# ElectronicCompass_T05.net
KiCad netlist of a schematic drawn in EAGLE
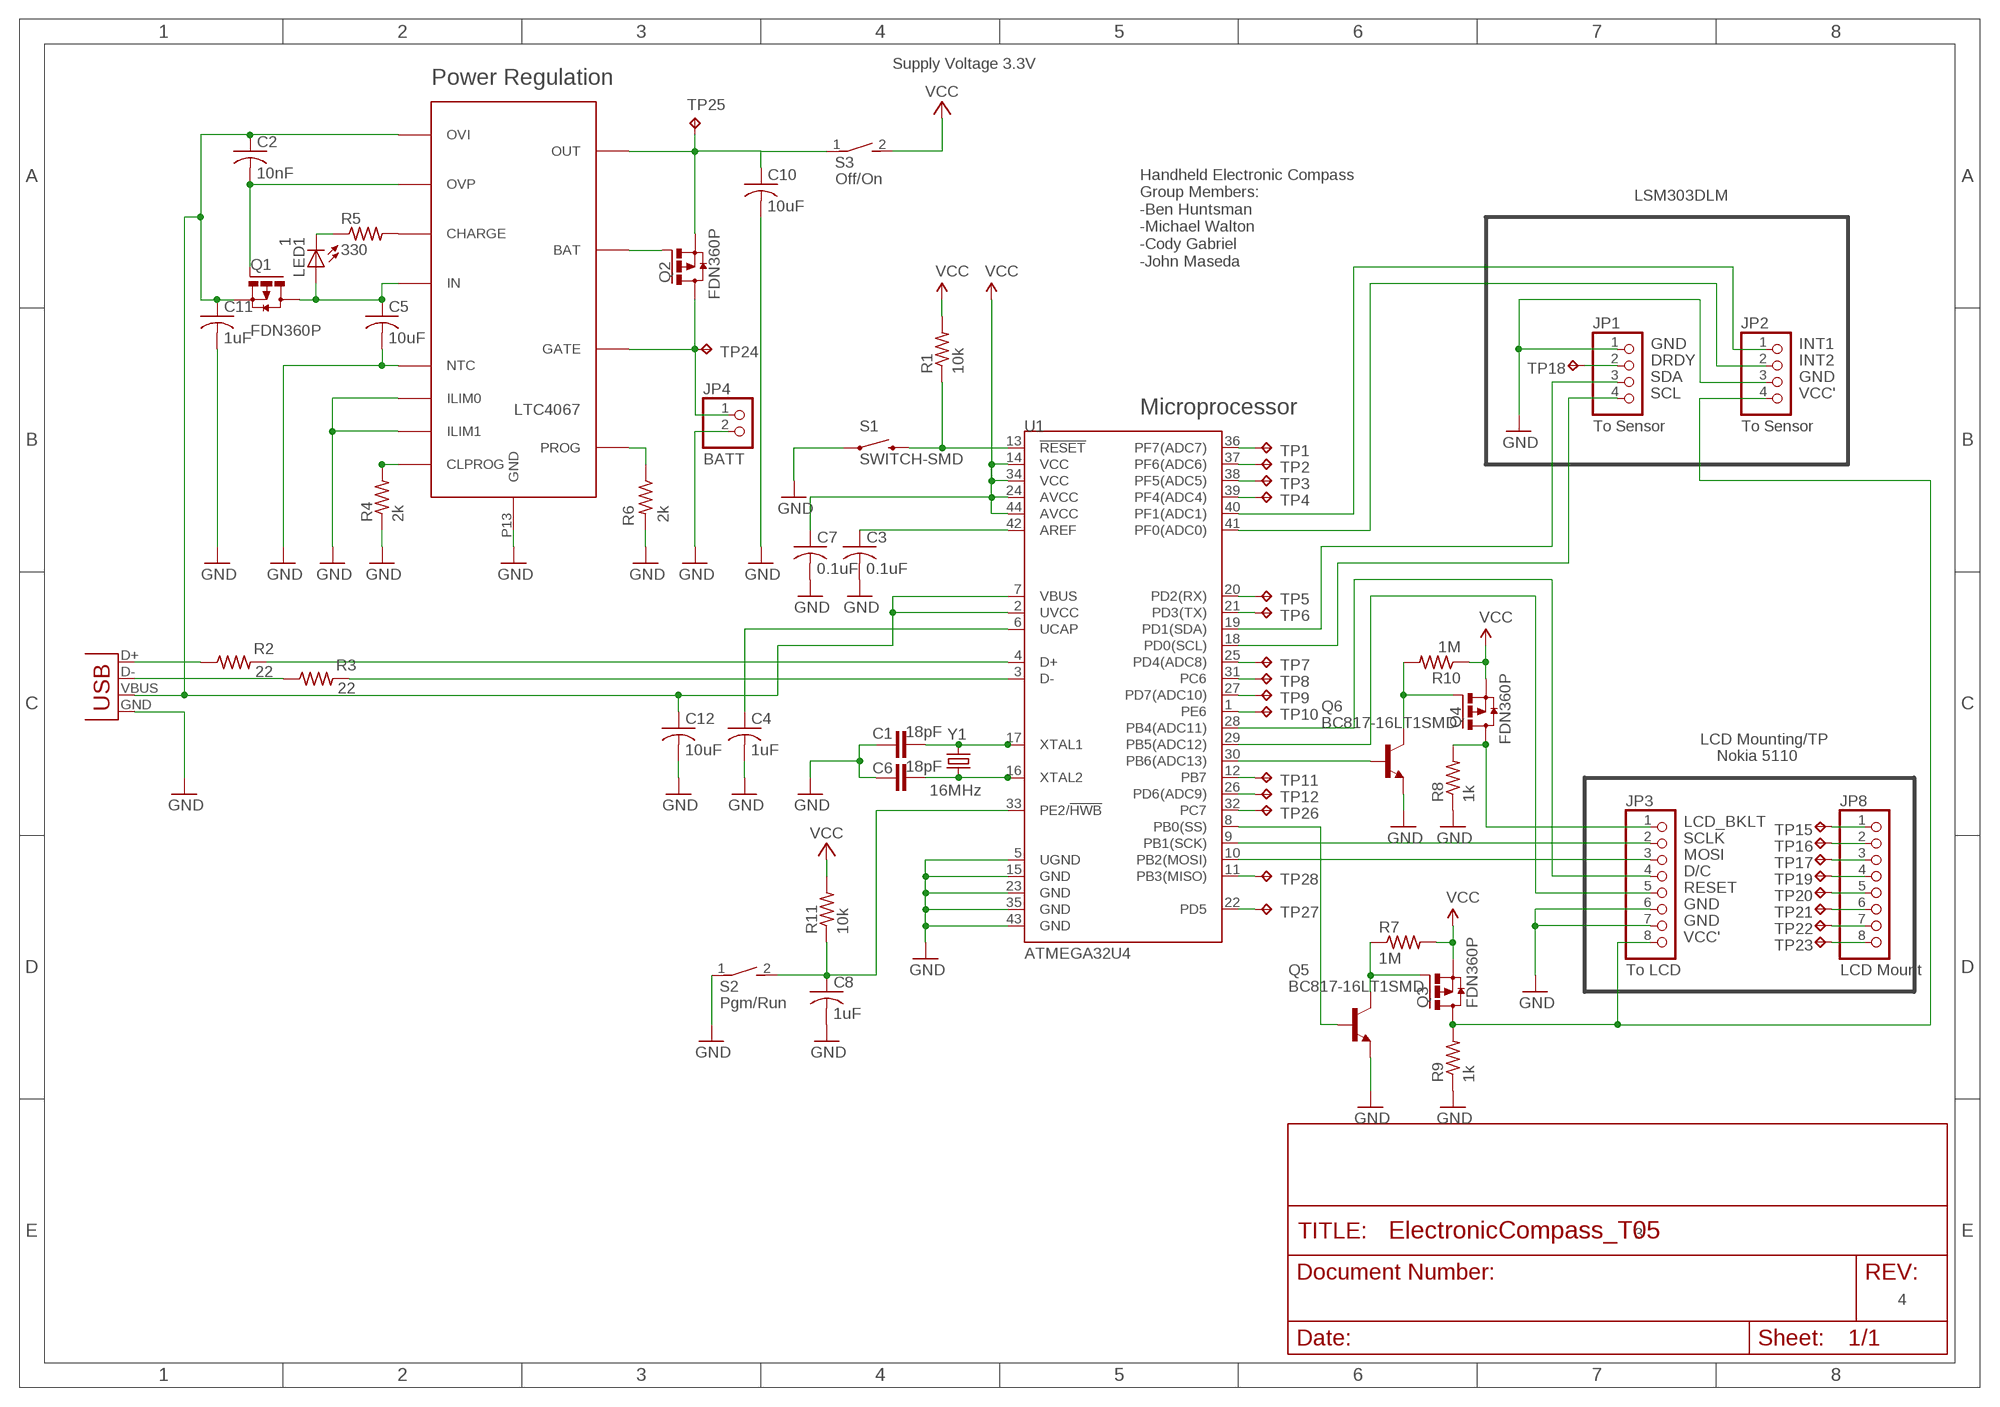
[diagram p0: schematic, sheet 1]

(export (version "E")
  (design (tool "Eeschema 10.0.6"))
  (components
    (comp (ref "C1")
      (value "18pF")
      (footprint "eagle-import:0402-CAP")
      (libsource (lib "eagle-import") (part "CAP0402-CAP"))
    )
    (comp (ref "C2")
      (value "10nF")
      (footprint "eagle-import:C0805")
      (libsource (lib "eagle-import") (part "C-USC0805"))
    )
    (comp (ref "C3")
      (value "0.1uF")
      (footprint "eagle-import:C0805")
      (libsource (lib "eagle-import") (part "C-USC0805"))
    )
    (comp (ref "C4")
      (value "1uF")
      (footprint "eagle-import:C0805")
      (libsource (lib "eagle-import") (part "C-USC0805"))
    )
    (comp (ref "C5")
      (value "10uF")
      (footprint "eagle-import:C0805")
      (libsource (lib "eagle-import") (part "C-USC0805"))
    )
    (comp (ref "C6")
      (value "18pF")
      (footprint "eagle-import:0402-CAP")
      (libsource (lib "eagle-import") (part "CAP0402-CAP"))
    )
    (comp (ref "C7")
      (value "0.1uF")
      (footprint "eagle-import:C0805")
      (libsource (lib "eagle-import") (part "C-USC0805"))
    )
    (comp (ref "C8")
      (value "1uF")
      (footprint "eagle-import:C0805")
      (libsource (lib "eagle-import") (part "C-USC0805"))
    )
    (comp (ref "C10")
      (value "10uF")
      (footprint "eagle-import:C0805")
      (libsource (lib "eagle-import") (part "C-USC0805"))
    )
    (comp (ref "C11")
      (value "1uF")
      (footprint "eagle-import:C0805")
      (libsource (lib "eagle-import") (part "C-USC0805"))
    )
    (comp (ref "C12")
      (value "10uF")
      (footprint "eagle-import:C0805")
      (libsource (lib "eagle-import") (part "C-USC0805"))
    )
    (comp (ref "JP1")
      (value "To Sensor")
      (footprint "eagle-import:1X04")
      (libsource (lib "eagle-import") (part "PINHD-1X4"))
    )
    (comp (ref "JP2")
      (value "To Sensor")
      (footprint "eagle-import:1X04")
      (libsource (lib "eagle-import") (part "PINHD-1X4"))
    )
    (comp (ref "JP3")
      (value "To LCD")
      (footprint "eagle-import:1X08")
      (libsource (lib "eagle-import") (part "PINHD-1X8"))
    )
    (comp (ref "JP4")
      (value "BATT")
      (footprint "eagle-import:1X02")
      (libsource (lib "eagle-import") (part "PINHD-1X2"))
    )
    (comp (ref "JP8")
      (value "LCD Mount")
      (footprint "eagle-import:1X08")
      (libsource (lib "eagle-import") (part "PINHD-1X8"))
    )
    (comp (ref "LED1")
      (value "1")
      (footprint "eagle-import:CHIPLED_0805")
      (libsource (lib "eagle-import") (part "LEDCHIPLED_0805"))
    )
    (comp (ref "Q1")
      (value "FDN360P")
      (footprint "eagle-import:SUPER-SOT3")
      (libsource (lib "eagle-import") (part "FDN360P"))
    )
    (comp (ref "Q2")
      (value "FDN360P")
      (footprint "eagle-import:SUPER-SOT3")
      (libsource (lib "eagle-import") (part "FDN360P"))
    )
    (comp (ref "Q3")
      (value "FDN360P")
      (footprint "eagle-import:SUPER-SOT3")
      (libsource (lib "eagle-import") (part "FDN360P"))
    )
    (comp (ref "Q4")
      (value "FDN360P")
      (footprint "eagle-import:SUPER-SOT3")
      (libsource (lib "eagle-import") (part "FDN360P"))
    )
    (comp (ref "Q5")
      (value "BC817-16LT1SMD")
      (footprint "eagle-import:SOT23-BEC")
      (libsource (lib "eagle-import") (part "BC817SMD-16LT1"))
    )
    (comp (ref "Q6")
      (value "BC817-16LT1SMD")
      (footprint "eagle-import:SOT23-BEC")
      (libsource (lib "eagle-import") (part "BC817SMD-16LT1"))
    )
    (comp (ref "R1")
      (value "10k")
      (footprint "eagle-import:M0805")
      (libsource (lib "eagle-import") (part "resistor_R-US_M0805"))
    )
    (comp (ref "R2")
      (value "22")
      (footprint "eagle-import:M0805")
      (libsource (lib "eagle-import") (part "resistor_R-US_M0805"))
    )
    (comp (ref "R3")
      (value "22")
      (footprint "eagle-import:M0805")
      (libsource (lib "eagle-import") (part "resistor_R-US_M0805"))
    )
    (comp (ref "R4")
      (value "2k")
      (footprint "eagle-import:M0805")
      (libsource (lib "eagle-import") (part "resistor_R-US_M0805"))
    )
    (comp (ref "R5")
      (value "330")
      (footprint "eagle-import:M0805")
      (libsource (lib "eagle-import") (part "resistor_R-US_M0805"))
    )
    (comp (ref "R6")
      (value "2k")
      (footprint "eagle-import:M0805")
      (libsource (lib "eagle-import") (part "resistor_R-US_M0805"))
    )
    (comp (ref "R7")
      (value "1M")
      (footprint "eagle-import:M0805")
      (libsource (lib "eagle-import") (part "resistor_R-US_M0805"))
    )
    (comp (ref "R8")
      (value "1k")
      (footprint "eagle-import:M0805")
      (libsource (lib "eagle-import") (part "R-US_M0805"))
    )
    (comp (ref "R9")
      (value "1k")
      (footprint "eagle-import:M0805")
      (libsource (lib "eagle-import") (part "resistor_R-US_M0805"))
    )
    (comp (ref "R10")
      (value "1M")
      (footprint "eagle-import:M0805")
      (libsource (lib "eagle-import") (part "resistor_R-US_M0805"))
    )
    (comp (ref "R11")
      (value "10k")
      (footprint "eagle-import:M0805")
      (libsource (lib "eagle-import") (part "resistor_R-US_M0805"))
    )
    (comp (ref "S1")
      (value "SWITCH-SMD")
      (footprint "eagle-import:TACTILE_SWITCH_SMD")
      (libsource (lib "eagle-import") (part "SWITCH-MOMENTARY-2SMD"))
    )
    (comp (ref "S2")
      (value "Pgm/Run")
      (footprint "eagle-import:DS-01")
      (libsource (lib "eagle-import") (part "DS01E"))
    )
    (comp (ref "S3")
      (value "Off/On")
      (footprint "eagle-import:DS-01")
      (libsource (lib "eagle-import") (part "DS01E"))
    )
    (comp (ref "TP1")
      (value "TPTP06R")
      (footprint "eagle-import:TP06R")
      (libsource (lib "eagle-import") (part "TPTP06R"))
    )
    (comp (ref "TP2")
      (value "TPTP06R")
      (footprint "eagle-import:TP06R")
      (libsource (lib "eagle-import") (part "TPTP06R"))
    )
    (comp (ref "TP3")
      (value "TPTP06R")
      (footprint "eagle-import:TP06R")
      (libsource (lib "eagle-import") (part "TPTP06R"))
    )
    (comp (ref "TP4")
      (value "TPTP06R")
      (footprint "eagle-import:TP06R")
      (libsource (lib "eagle-import") (part "TPTP06R"))
    )
    (comp (ref "TP5")
      (value "TPTP06R")
      (footprint "eagle-import:TP06R")
      (libsource (lib "eagle-import") (part "TPTP06R"))
    )
    (comp (ref "TP6")
      (value "TPTP06R")
      (footprint "eagle-import:TP06R")
      (libsource (lib "eagle-import") (part "TPTP06R"))
    )
    (comp (ref "TP7")
      (value "TPTP06R")
      (footprint "eagle-import:TP06R")
      (libsource (lib "eagle-import") (part "TPTP06R"))
    )
    (comp (ref "TP8")
      (value "TPTP06R")
      (footprint "eagle-import:TP06R")
      (libsource (lib "eagle-import") (part "TPTP06R"))
    )
    (comp (ref "TP9")
      (value "TPTP06R")
      (footprint "eagle-import:TP06R")
      (libsource (lib "eagle-import") (part "TPTP06R"))
    )
    (comp (ref "TP10")
      (value "TPTP06R")
      (footprint "eagle-import:TP06R")
      (libsource (lib "eagle-import") (part "TPTP06R"))
    )
    (comp (ref "TP11")
      (value "TPTP06R")
      (footprint "eagle-import:TP06R")
      (libsource (lib "eagle-import") (part "TPTP06R"))
    )
    (comp (ref "TP12")
      (value "TPTP06R")
      (footprint "eagle-import:TP06R")
      (libsource (lib "eagle-import") (part "TPTP06R"))
    )
    (comp (ref "TP15")
      (value "TPTP06R")
      (footprint "eagle-import:TP06R")
      (libsource (lib "eagle-import") (part "TPTP06R"))
    )
    (comp (ref "TP16")
      (value "TPTP06R")
      (footprint "eagle-import:TP06R")
      (libsource (lib "eagle-import") (part "TPTP06R"))
    )
    (comp (ref "TP17")
      (value "TPTP06R")
      (footprint "eagle-import:TP06R")
      (libsource (lib "eagle-import") (part "TPTP06R"))
    )
    (comp (ref "TP18")
      (value "TPTP06R")
      (footprint "eagle-import:TP06R")
      (libsource (lib "eagle-import") (part "TPTP06R"))
    )
    (comp (ref "TP19")
      (value "TPTP06R")
      (footprint "eagle-import:TP06R")
      (libsource (lib "eagle-import") (part "TPTP06R"))
    )
    (comp (ref "TP20")
      (value "TPTP06R")
      (footprint "eagle-import:TP06R")
      (libsource (lib "eagle-import") (part "TPTP06R"))
    )
    (comp (ref "TP21")
      (value "TPTP06R")
      (footprint "eagle-import:TP06R")
      (libsource (lib "eagle-import") (part "TPTP06R"))
    )
    (comp (ref "TP22")
      (value "TPTP06R")
      (footprint "eagle-import:TP06R")
      (libsource (lib "eagle-import") (part "TPTP06R"))
    )
    (comp (ref "TP23")
      (value "TPTP06R")
      (footprint "eagle-import:TP06R")
      (libsource (lib "eagle-import") (part "TPTP06R"))
    )
    (comp (ref "TP24")
      (value "TPTP06R")
      (footprint "eagle-import:TP06R")
      (libsource (lib "eagle-import") (part "TPTP06R"))
    )
    (comp (ref "TP25")
      (value "TPTP06R")
      (footprint "eagle-import:TP06R")
      (libsource (lib "eagle-import") (part "TPTP06R"))
    )
    (comp (ref "TP26")
      (value "TPTP06R")
      (footprint "eagle-import:TP06R")
      (libsource (lib "eagle-import") (part "TPTP06R"))
    )
    (comp (ref "TP27")
      (value "TPTP06R")
      (footprint "eagle-import:TP06R")
      (libsource (lib "eagle-import") (part "TPTP06R"))
    )
    (comp (ref "TP28")
      (value "TPTP06R")
      (footprint "eagle-import:TP06R")
      (libsource (lib "eagle-import") (part "TPTP06R"))
    )
    (comp (ref "U$1")
      (value "LTC4067")
      (footprint "eagle-import:DFN-12")
      (libsource (lib "eagle-import") (part "LTC4067"))
    )
    (comp (ref "U1")
      (value "ATMEGA32U4")
      (footprint "eagle-import:QFN-44-NOPAD")
      (libsource (lib "eagle-import") (part "ATMEGA32U4QFN2"))
    )
    (comp (ref "X1")
      (value "USBSMD")
      (footprint "eagle-import:USB-MINIB")
      (libsource (lib "eagle-import") (part "USBSMD"))
    )
    (comp (ref "Y1")
      (value "16MHz")
      (footprint "eagle-import:CRYSTAL-SMD-5X3")
      (libsource (lib "eagle-import") (part "CRYSTAL5X3"))
    )
  )
  (nets
    (net (code "1") (name "/DRDY") (class "Default")
      (node (ref "JP1") (pin "2") (pinfunction "2_2") (pintype "passive"))
      (node (ref "TP18") (pin "TP") (pinfunction "TP_TP") (pintype "input"))
    )
    (net (code "2") (name "/D{slash}C") (class "Default")
      (node (ref "JP3") (pin "4") (pinfunction "4_4") (pintype "passive"))
      (node (ref "U1") (pin "28") (pinfunction "PB4(ADC11)_28") (pintype "bidirectional"))
    )
    (net (code "3") (name "/INT1") (class "Default")
      (node (ref "JP2") (pin "1") (pinfunction "1_1") (pintype "passive"))
      (node (ref "U1") (pin "40") (pinfunction "PF1(ADC1)_40") (pintype "bidirectional"))
    )
    (net (code "4") (name "/INT2") (class "Default")
      (node (ref "JP2") (pin "2") (pinfunction "2_2") (pintype "passive"))
      (node (ref "U1") (pin "41") (pinfunction "PF0(ADC0)_41") (pintype "bidirectional"))
    )
    (net (code "5") (name "/LCD_BKLT") (class "Default")
      (node (ref "JP3") (pin "1") (pinfunction "1_1") (pintype "passive"))
      (node (ref "Q4") (pin "3") (pinfunction "D_3") (pintype "passive"))
      (node (ref "R8") (pin "2") (pinfunction "2_2") (pintype "passive"))
    )
    (net (code "6") (name "/MOSI") (class "Default")
      (node (ref "JP3") (pin "3") (pinfunction "3_3") (pintype "passive"))
      (node (ref "U1") (pin "10") (pinfunction "PB2(MOSI)_10") (pintype "bidirectional"))
    )
    (net (code "7") (name "/RESET") (class "Default")
      (node (ref "JP3") (pin "5") (pinfunction "5_5") (pintype "passive"))
      (node (ref "U1") (pin "29") (pinfunction "PB5(ADC12)_29") (pintype "bidirectional"))
    )
    (net (code "8") (name "/SCL") (class "Default")
      (node (ref "JP1") (pin "4") (pinfunction "4_4") (pintype "passive"))
      (node (ref "U1") (pin "18") (pinfunction "PD0(SCL)_18") (pintype "bidirectional"))
    )
    (net (code "9") (name "/SCLK") (class "Default")
      (node (ref "JP3") (pin "2") (pinfunction "2_2") (pintype "passive"))
      (node (ref "U1") (pin "9") (pinfunction "PB1(SCK)_9") (pintype "bidirectional"))
    )
    (net (code "10") (name "/SDA") (class "Default")
      (node (ref "JP1") (pin "3") (pinfunction "3_3") (pintype "passive"))
      (node (ref "U1") (pin "19") (pinfunction "PD1(SDA)_19") (pintype "bidirectional"))
    )
    (net (code "11") (name "/VCC'") (class "Default")
      (node (ref "JP2") (pin "4") (pinfunction "4_4") (pintype "passive"))
      (node (ref "JP3") (pin "8") (pinfunction "8_8") (pintype "passive"))
      (node (ref "Q3") (pin "3") (pinfunction "D_3") (pintype "passive"))
      (node (ref "R9") (pin "2") (pinfunction "2_2") (pintype "passive"))
    )
    (net (code "12") (name "GND") (class "Default")
      (node (ref "C1") (pin "1") (pinfunction "1_1") (pintype "passive"))
      (node (ref "C10") (pin "2") (pinfunction "2_2") (pintype "passive"))
      (node (ref "C11") (pin "2") (pinfunction "2_2") (pintype "passive"))
      (node (ref "C12") (pin "2") (pinfunction "2_2") (pintype "passive"))
      (node (ref "C3") (pin "2") (pinfunction "2_2") (pintype "passive"))
      (node (ref "C4") (pin "2") (pinfunction "2_2") (pintype "passive"))
      (node (ref "C5") (pin "2") (pinfunction "2_2") (pintype "passive"))
      (node (ref "C6") (pin "1") (pinfunction "1_1") (pintype "passive"))
      (node (ref "C7") (pin "2") (pinfunction "2_2") (pintype "passive"))
      (node (ref "C8") (pin "2") (pinfunction "2_2") (pintype "passive"))
      (node (ref "JP1") (pin "1") (pinfunction "1_1") (pintype "passive"))
      (node (ref "JP2") (pin "3") (pinfunction "3_3") (pintype "passive"))
      (node (ref "JP3") (pin "6") (pinfunction "6_6") (pintype "passive"))
      (node (ref "JP3") (pin "7") (pinfunction "7_7") (pintype "passive"))
      (node (ref "JP4") (pin "2") (pinfunction "2_2") (pintype "passive"))
      (node (ref "Q5") (pin "E") (pinfunction "E_E") (pintype "passive"))
      (node (ref "Q6") (pin "E") (pinfunction "E_E") (pintype "passive"))
      (node (ref "R4") (pin "1") (pinfunction "1_1") (pintype "passive"))
      (node (ref "R6") (pin "2") (pinfunction "2_2") (pintype "passive"))
      (node (ref "R8") (pin "1") (pinfunction "1_1") (pintype "passive"))
      (node (ref "R9") (pin "1") (pinfunction "1_1") (pintype "passive"))
      (node (ref "S1") (pin "1") (pinfunction "1_1") (pintype "passive"))
      (node (ref "S2") (pin "1") (pinfunction "1_1") (pintype "passive"))
      (node (ref "U$1") (pin "P13") (pinfunction "GND_P13") (pintype "bidirectional"))
      (node (ref "U$1") (pin "P3") (pinfunction "NTC_P3") (pintype "bidirectional"))
      (node (ref "U$1") (pin "P4") (pinfunction "ILIM0_P4") (pintype "bidirectional"))
      (node (ref "U$1") (pin "P5") (pinfunction "ILIM1_P5") (pintype "bidirectional"))
      (node (ref "U1") (pin "15") (pinfunction "GND_15") (pintype "bidirectional"))
      (node (ref "U1") (pin "23") (pinfunction "GND_23") (pintype "bidirectional"))
      (node (ref "U1") (pin "35") (pinfunction "GND_35") (pintype "bidirectional"))
      (node (ref "U1") (pin "43") (pinfunction "GND_43") (pintype "bidirectional"))
      (node (ref "U1") (pin "5") (pinfunction "UGND_5") (pintype "bidirectional"))
      (node (ref "X1") (pin "GND") (pinfunction "GND_GND") (pintype "bidirectional"))
    )
    (net (code "13") (name "Net-(JP8-Pad1)") (class "Default")
      (node (ref "JP8") (pin "1") (pinfunction "1_1") (pintype "passive"))
      (node (ref "TP15") (pin "TP") (pinfunction "TP_TP") (pintype "input"))
    )
    (net (code "14") (name "Net-(JP8-Pad2)") (class "Default")
      (node (ref "JP8") (pin "2") (pinfunction "2_2") (pintype "passive"))
      (node (ref "TP16") (pin "TP") (pinfunction "TP_TP") (pintype "input"))
    )
    (net (code "15") (name "Net-(JP8-Pad3)") (class "Default")
      (node (ref "JP8") (pin "3") (pinfunction "3_3") (pintype "passive"))
      (node (ref "TP17") (pin "TP") (pinfunction "TP_TP") (pintype "input"))
    )
    (net (code "16") (name "Net-(JP8-Pad4)") (class "Default")
      (node (ref "JP8") (pin "4") (pinfunction "4_4") (pintype "passive"))
      (node (ref "TP19") (pin "TP") (pinfunction "TP_TP") (pintype "input"))
    )
    (net (code "17") (name "Net-(JP8-Pad5)") (class "Default")
      (node (ref "JP8") (pin "5") (pinfunction "5_5") (pintype "passive"))
      (node (ref "TP20") (pin "TP") (pinfunction "TP_TP") (pintype "input"))
    )
    (net (code "18") (name "Net-(JP8-Pad6)") (class "Default")
      (node (ref "JP8") (pin "6") (pinfunction "6_6") (pintype "passive"))
      (node (ref "TP21") (pin "TP") (pinfunction "TP_TP") (pintype "input"))
    )
    (net (code "19") (name "Net-(JP8-Pad7)") (class "Default")
      (node (ref "JP8") (pin "7") (pinfunction "7_7") (pintype "passive"))
      (node (ref "TP22") (pin "TP") (pinfunction "TP_TP") (pintype "input"))
    )
    (net (code "20") (name "Net-(JP8-Pad8)") (class "Default")
      (node (ref "JP8") (pin "8") (pinfunction "8_8") (pintype "passive"))
      (node (ref "TP23") (pin "TP") (pinfunction "TP_TP") (pintype "input"))
    )
    (net (code "21") (name "Net-(LED1-PadC)") (class "Default")
      (node (ref "LED1") (pin "C") (pinfunction "C_C") (pintype "passive"))
      (node (ref "R5") (pin "1") (pinfunction "1_1") (pintype "passive"))
    )
    (net (code "22") (name "Net-(Q1-D)") (class "Default")
      (node (ref "C5") (pin "1") (pinfunction "1_1") (pintype "passive"))
      (node (ref "LED1") (pin "A") (pinfunction "A_A") (pintype "passive"))
      (node (ref "Q1") (pin "3") (pinfunction "D_3") (pintype "passive"))
      (node (ref "U$1") (pin "P12") (pinfunction "IN_P12") (pintype "bidirectional"))
    )
    (net (code "23") (name "Net-(Q1-G)") (class "Default")
      (node (ref "C2") (pin "2") (pinfunction "2_2") (pintype "passive"))
      (node (ref "Q1") (pin "1") (pinfunction "G_1") (pintype "passive"))
      (node (ref "U$1") (pin "P7") (pinfunction "OVP_P7") (pintype "bidirectional"))
    )
    (net (code "24") (name "Net-(Q1-S)") (class "Default")
      (node (ref "C11") (pin "1") (pinfunction "1_1") (pintype "passive"))
      (node (ref "C12") (pin "1") (pinfunction "1_1") (pintype "passive"))
      (node (ref "C2") (pin "1") (pinfunction "1_1") (pintype "passive"))
      (node (ref "Q1") (pin "2") (pinfunction "S_2") (pintype "passive"))
      (node (ref "U$1") (pin "P6") (pinfunction "OVI_P6") (pintype "bidirectional"))
      (node (ref "U1") (pin "2") (pinfunction "UVCC_2") (pintype "bidirectional"))
      (node (ref "U1") (pin "7") (pinfunction "VBUS_7") (pintype "bidirectional"))
      (node (ref "X1") (pin "VBUS") (pinfunction "VBUS_VBUS") (pintype "bidirectional"))
    )
    (net (code "25") (name "Net-(Q2-D)") (class "Default")
      (node (ref "JP4") (pin "1") (pinfunction "1_1") (pintype "passive"))
      (node (ref "Q2") (pin "3") (pinfunction "D_3") (pintype "passive"))
      (node (ref "TP24") (pin "TP") (pinfunction "TP_TP") (pintype "input"))
      (node (ref "U$1") (pin "P9") (pinfunction "GATE_P9") (pintype "bidirectional"))
    )
    (net (code "26") (name "Net-(Q2-G)") (class "Default")
      (node (ref "Q2") (pin "1") (pinfunction "G_1") (pintype "passive"))
      (node (ref "U$1") (pin "P10") (pinfunction "BAT_P10") (pintype "bidirectional"))
    )
    (net (code "27") (name "Net-(Q2-S)") (class "Default")
      (node (ref "C10") (pin "1") (pinfunction "1_1") (pintype "passive"))
      (node (ref "Q2") (pin "2") (pinfunction "S_2") (pintype "passive"))
      (node (ref "S3") (pin "1") (pinfunction "1_1") (pintype "passive"))
      (node (ref "TP25") (pin "TP") (pinfunction "TP_TP") (pintype "input"))
      (node (ref "U$1") (pin "P11") (pinfunction "OUT_P11") (pintype "bidirectional"))
    )
    (net (code "28") (name "Net-(Q3-G)") (class "Default")
      (node (ref "Q3") (pin "1") (pinfunction "G_1") (pintype "passive"))
      (node (ref "Q5") (pin "C") (pinfunction "C_C") (pintype "passive"))
      (node (ref "R7") (pin "1") (pinfunction "1_1") (pintype "passive"))
    )
    (net (code "29") (name "Net-(Q4-G)") (class "Default")
      (node (ref "Q4") (pin "1") (pinfunction "G_1") (pintype "passive"))
      (node (ref "Q6") (pin "C") (pinfunction "C_C") (pintype "passive"))
      (node (ref "R10") (pin "2") (pinfunction "2_2") (pintype "passive"))
    )
    (net (code "30") (name "Net-(R2-Pad1)") (class "Default")
      (node (ref "R2") (pin "1") (pinfunction "1_1") (pintype "passive"))
      (node (ref "X1") (pin "D+") (pinfunction "D+_D+") (pintype "bidirectional"))
    )
    (net (code "31") (name "Net-(R3-Pad1)") (class "Default")
      (node (ref "R3") (pin "1") (pinfunction "1_1") (pintype "passive"))
      (node (ref "X1") (pin "D-") (pinfunction "D-_D-") (pintype "bidirectional"))
    )
    (net (code "32") (name "Net-(S1-2)") (class "Default")
      (node (ref "R1") (pin "1") (pinfunction "1_1") (pintype "passive"))
      (node (ref "S1") (pin "3") (pinfunction "2_3") (pintype "passive"))
      (node (ref "U1") (pin "13") (pinfunction "~{RESET}_13") (pintype "bidirectional"))
    )
    (net (code "33") (name "Net-(U$1-CHARGE)") (class "Default")
      (node (ref "R5") (pin "2") (pinfunction "2_2") (pintype "passive"))
      (node (ref "U$1") (pin "P2") (pinfunction "CHARGE_P2") (pintype "bidirectional"))
    )
    (net (code "34") (name "Net-(U$1-CLPROG)") (class "Default")
      (node (ref "R4") (pin "2") (pinfunction "2_2") (pintype "passive"))
      (node (ref "U$1") (pin "P1") (pinfunction "CLPROG_P1") (pintype "bidirectional"))
    )
    (net (code "35") (name "Net-(U$1-PROG)") (class "Default")
      (node (ref "R6") (pin "1") (pinfunction "1_1") (pintype "passive"))
      (node (ref "U$1") (pin "P8") (pinfunction "PROG_P8") (pintype "bidirectional"))
    )
    (net (code "36") (name "Net-(U1-AREF)") (class "Default")
      (node (ref "C3") (pin "1") (pinfunction "1_1") (pintype "passive"))
      (node (ref "U1") (pin "42") (pinfunction "AREF_42") (pintype "bidirectional"))
    )
    (net (code "37") (name "Net-(U1-D+)") (class "Default")
      (node (ref "R2") (pin "2") (pinfunction "2_2") (pintype "passive"))
      (node (ref "U1") (pin "4") (pinfunction "D+_4") (pintype "bidirectional"))
    )
    (net (code "38") (name "Net-(U1-D-)") (class "Default")
      (node (ref "R3") (pin "2") (pinfunction "2_2") (pintype "passive"))
      (node (ref "U1") (pin "3") (pinfunction "D-_3") (pintype "bidirectional"))
    )
    (net (code "39") (name "Net-(U1-PB0(SS))") (class "Default")
      (node (ref "Q5") (pin "B") (pinfunction "B_B") (pintype "passive"))
      (node (ref "U1") (pin "8") (pinfunction "PB0(SS)_8") (pintype "bidirectional"))
    )
    (net (code "40") (name "Net-(U1-PB3(MISO))") (class "Default")
      (node (ref "TP28") (pin "TP") (pinfunction "TP_TP") (pintype "input"))
      (node (ref "U1") (pin "11") (pinfunction "PB3(MISO)_11") (pintype "bidirectional"))
    )
    (net (code "41") (name "Net-(U1-PB6(ADC13))") (class "Default")
      (node (ref "Q6") (pin "B") (pinfunction "B_B") (pintype "passive"))
      (node (ref "U1") (pin "30") (pinfunction "PB6(ADC13)_30") (pintype "bidirectional"))
    )
    (net (code "42") (name "Net-(U1-PB7)") (class "Default")
      (node (ref "TP11") (pin "TP") (pinfunction "TP_TP") (pintype "input"))
      (node (ref "U1") (pin "12") (pinfunction "PB7_12") (pintype "bidirectional"))
    )
    (net (code "43") (name "Net-(U1-PC6)") (class "Default")
      (node (ref "TP8") (pin "TP") (pinfunction "TP_TP") (pintype "input"))
      (node (ref "U1") (pin "31") (pinfunction "PC6_31") (pintype "bidirectional"))
    )
    (net (code "44") (name "Net-(U1-PC7)") (class "Default")
      (node (ref "TP26") (pin "TP") (pinfunction "TP_TP") (pintype "input"))
      (node (ref "U1") (pin "32") (pinfunction "PC7_32") (pintype "bidirectional"))
    )
    (net (code "45") (name "Net-(U1-PD2(RX))") (class "Default")
      (node (ref "TP5") (pin "TP") (pinfunction "TP_TP") (pintype "input"))
      (node (ref "U1") (pin "20") (pinfunction "PD2(RX)_20") (pintype "bidirectional"))
    )
    (net (code "46") (name "Net-(U1-PD3(TX))") (class "Default")
      (node (ref "TP6") (pin "TP") (pinfunction "TP_TP") (pintype "input"))
      (node (ref "U1") (pin "21") (pinfunction "PD3(TX)_21") (pintype "bidirectional"))
    )
    (net (code "47") (name "Net-(U1-PD4(ADC8))") (class "Default")
      (node (ref "TP7") (pin "TP") (pinfunction "TP_TP") (pintype "input"))
      (node (ref "U1") (pin "25") (pinfunction "PD4(ADC8)_25") (pintype "bidirectional"))
    )
    (net (code "48") (name "Net-(U1-PD5)") (class "Default")
      (node (ref "TP27") (pin "TP") (pinfunction "TP_TP") (pintype "input"))
      (node (ref "U1") (pin "22") (pinfunction "PD5_22") (pintype "bidirectional"))
    )
    (net (code "49") (name "Net-(U1-PD6(ADC9))") (class "Default")
      (node (ref "TP12") (pin "TP") (pinfunction "TP_TP") (pintype "input"))
      (node (ref "U1") (pin "26") (pinfunction "PD6(ADC9)_26") (pintype "bidirectional"))
    )
    (net (code "50") (name "Net-(U1-PD7(ADC10))") (class "Default")
      (node (ref "TP9") (pin "TP") (pinfunction "TP_TP") (pintype "input"))
      (node (ref "U1") (pin "27") (pinfunction "PD7(ADC10)_27") (pintype "bidirectional"))
    )
    (net (code "51") (name "Net-(U1-PE2{slash}~{HWB})") (class "Default")
      (node (ref "C8") (pin "1") (pinfunction "1_1") (pintype "passive"))
      (node (ref "R11") (pin "1") (pinfunction "1_1") (pintype "passive"))
      (node (ref "S2") (pin "2") (pinfunction "2_2") (pintype "passive"))
      (node (ref "U1") (pin "33") (pinfunction "PE2/~{HWB}_33") (pintype "bidirectional"))
    )
    (net (code "52") (name "Net-(U1-PE6)") (class "Default")
      (node (ref "TP10") (pin "TP") (pinfunction "TP_TP") (pintype "input"))
      (node (ref "U1") (pin "1") (pinfunction "PE6_1") (pintype "bidirectional"))
    )
    (net (code "53") (name "Net-(U1-PF4(ADC4))") (class "Default")
      (node (ref "TP4") (pin "TP") (pinfunction "TP_TP") (pintype "input"))
      (node (ref "U1") (pin "39") (pinfunction "PF4(ADC4)_39") (pintype "bidirectional"))
    )
    (net (code "54") (name "Net-(U1-PF5(ADC5))") (class "Default")
      (node (ref "TP3") (pin "TP") (pinfunction "TP_TP") (pintype "input"))
      (node (ref "U1") (pin "38") (pinfunction "PF5(ADC5)_38") (pintype "bidirectional"))
    )
    (net (code "55") (name "Net-(U1-PF6(ADC6))") (class "Default")
      (node (ref "TP2") (pin "TP") (pinfunction "TP_TP") (pintype "input"))
      (node (ref "U1") (pin "37") (pinfunction "PF6(ADC6)_37") (pintype "bidirectional"))
    )
    (net (code "56") (name "Net-(U1-PF7(ADC7))") (class "Default")
      (node (ref "TP1") (pin "TP") (pinfunction "TP_TP") (pintype "input"))
      (node (ref "U1") (pin "36") (pinfunction "PF7(ADC7)_36") (pintype "bidirectional"))
    )
    (net (code "57") (name "Net-(U1-UCAP)") (class "Default")
      (node (ref "C4") (pin "1") (pinfunction "1_1") (pintype "passive"))
      (node (ref "U1") (pin "6") (pinfunction "UCAP_6") (pintype "bidirectional"))
    )
    (net (code "58") (name "Net-(U1-XTAL1)") (class "Default")
      (node (ref "C1") (pin "2") (pinfunction "2_2") (pintype "passive"))
      (node (ref "U1") (pin "17") (pinfunction "XTAL1_17") (pintype "bidirectional"))
      (node (ref "Y1") (pin "3") (pinfunction "2_3") (pintype "passive"))
    )
    (net (code "59") (name "Net-(U1-XTAL2)") (class "Default")
      (node (ref "C6") (pin "2") (pinfunction "2_2") (pintype "passive"))
      (node (ref "U1") (pin "16") (pinfunction "XTAL2_16") (pintype "bidirectional"))
      (node (ref "Y1") (pin "1") (pinfunction "1_1") (pintype "passive"))
    )
    (net (code "60") (name "VCC") (class "Default")
      (node (ref "C7") (pin "1") (pinfunction "1_1") (pintype "passive"))
      (node (ref "Q3") (pin "2") (pinfunction "S_2") (pintype "passive"))
      (node (ref "Q4") (pin "2") (pinfunction "S_2") (pintype "passive"))
      (node (ref "R1") (pin "2") (pinfunction "2_2") (pintype "passive"))
      (node (ref "R10") (pin "1") (pinfunction "1_1") (pintype "passive"))
      (node (ref "R11") (pin "2") (pinfunction "2_2") (pintype "passive"))
      (node (ref "R7") (pin "2") (pinfunction "2_2") (pintype "passive"))
      (node (ref "S3") (pin "2") (pinfunction "2_2") (pintype "passive"))
      (node (ref "U1") (pin "14") (pinfunction "VCC_14") (pintype "bidirectional"))
      (node (ref "U1") (pin "24") (pinfunction "AVCC_24") (pintype "bidirectional"))
      (node (ref "U1") (pin "34") (pinfunction "VCC_34") (pintype "bidirectional"))
      (node (ref "U1") (pin "44") (pinfunction "AVCC_44") (pintype "bidirectional"))
    )
  )
)
